# usb_isolated_uart_x2.net
KiCad netlist of a schematic drawn in Altium Designer
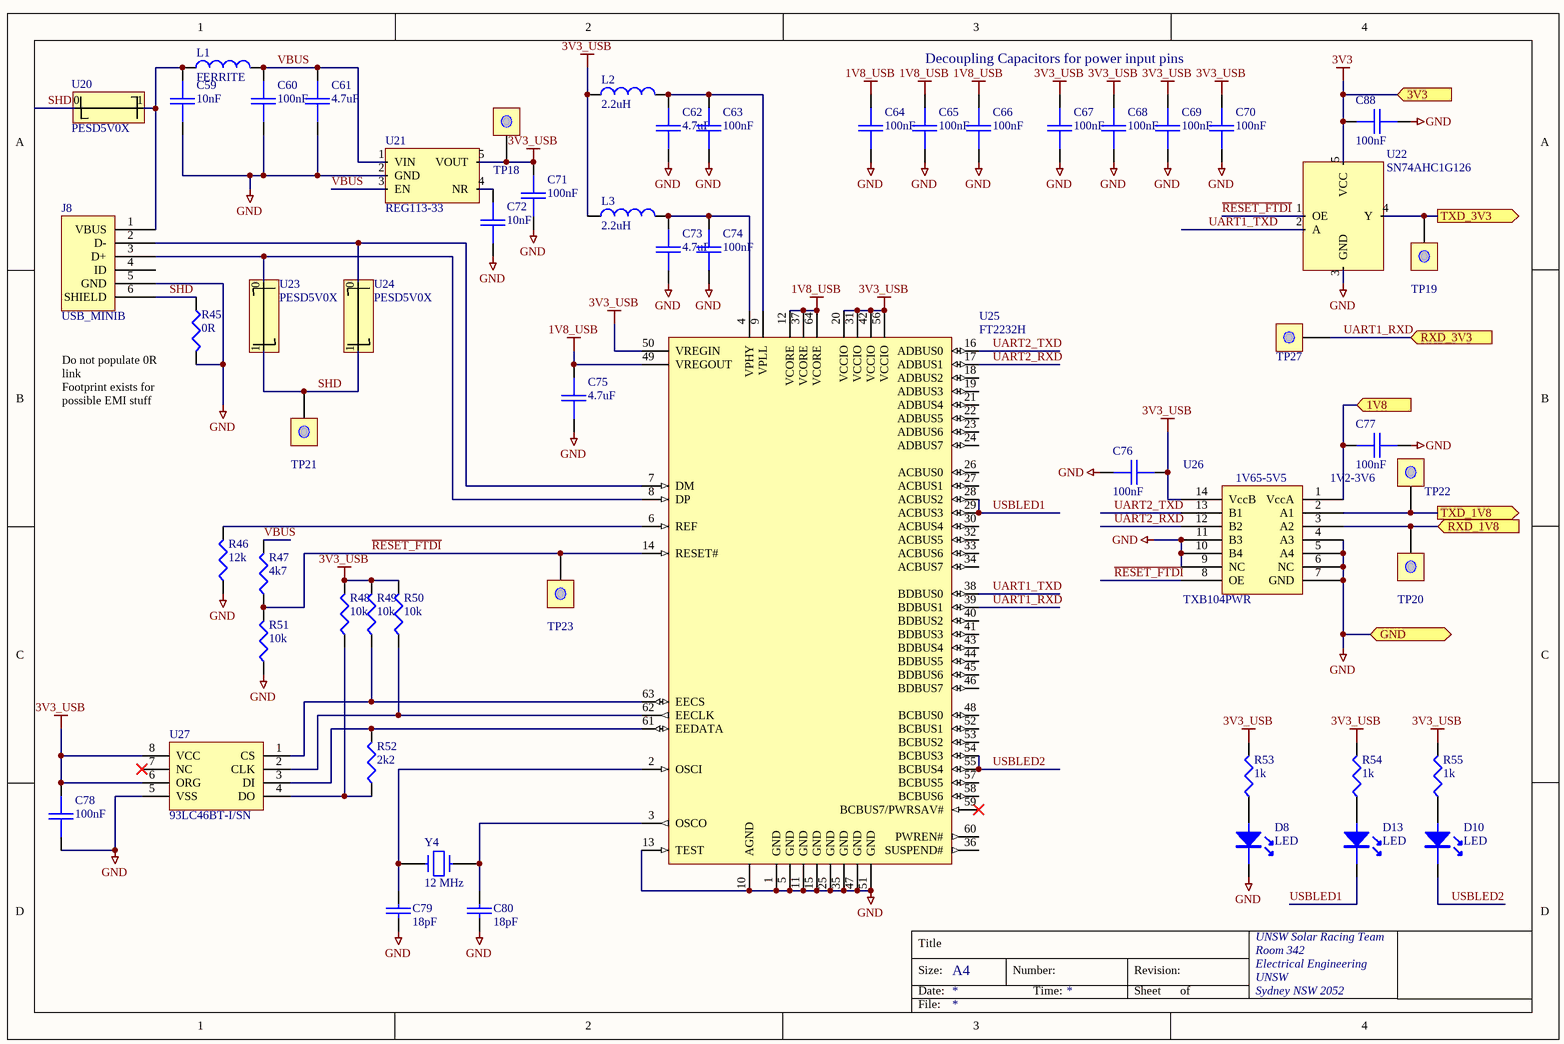
[diagram p0: usb_isolated_uart_x2.SchDoc]

(export (version "E")
  (design (tool "Eeschema 10.0.6"))
  (components
    (comp (ref "C59")
      (value "10nF")
      (footprint "0603")
      (description "Capacitor")
      (libsource (lib "RCLDQ") (part "CAP"))
    )
    (comp (ref "C60")
      (value "100nF")
      (footprint "0603")
      (description "Capacitor")
      (libsource (lib "RCLDQ") (part "CAP"))
    )
    (comp (ref "C61")
      (value "4.7uF")
      (footprint "0603")
      (description "Capacitor")
      (libsource (lib "RCLDQ") (part "CAP"))
    )
    (comp (ref "C62")
      (value "4.7uF")
      (footprint "0603")
      (description "Capacitor")
      (libsource (lib "RCLDQ") (part "CAP"))
    )
    (comp (ref "C63")
      (value "100nF")
      (footprint "0603")
      (description "Capacitor")
      (libsource (lib "RCLDQ") (part "CAP"))
    )
    (comp (ref "C64")
      (value "100nF")
      (footprint "0603")
      (description "Capacitor")
      (libsource (lib "RCLDQ") (part "CAP"))
    )
    (comp (ref "C65")
      (value "100nF")
      (footprint "0603")
      (description "Capacitor")
      (libsource (lib "RCLDQ") (part "CAP"))
    )
    (comp (ref "C66")
      (value "100nF")
      (footprint "0603")
      (description "Capacitor")
      (libsource (lib "RCLDQ") (part "CAP"))
    )
    (comp (ref "C67")
      (value "100nF")
      (footprint "0603")
      (description "Capacitor")
      (libsource (lib "RCLDQ") (part "CAP"))
    )
    (comp (ref "C68")
      (value "100nF")
      (footprint "0603")
      (description "Capacitor")
      (libsource (lib "RCLDQ") (part "CAP"))
    )
    (comp (ref "C69")
      (value "100nF")
      (footprint "0603")
      (description "Capacitor")
      (libsource (lib "RCLDQ") (part "CAP"))
    )
    (comp (ref "C70")
      (value "100nF")
      (footprint "0603")
      (description "Capacitor")
      (libsource (lib "RCLDQ") (part "CAP"))
    )
    (comp (ref "C71")
      (value "100nF")
      (footprint "0603")
      (description "Capacitor")
      (libsource (lib "RCLDQ") (part "CAP"))
    )
    (comp (ref "C72")
      (value "10nF")
      (footprint "0603")
      (description "Capacitor")
      (libsource (lib "RCLDQ") (part "CAP"))
    )
    (comp (ref "C73")
      (value "4.7uF")
      (footprint "0603")
      (description "Capacitor")
      (libsource (lib "RCLDQ") (part "CAP"))
    )
    (comp (ref "C74")
      (value "100nF")
      (footprint "0603")
      (description "Capacitor")
      (libsource (lib "RCLDQ") (part "CAP"))
    )
    (comp (ref "C75")
      (value "4.7uF")
      (footprint "0603")
      (description "Capacitor")
      (libsource (lib "RCLDQ") (part "CAP"))
    )
    (comp (ref "C76")
      (value "100nF")
      (footprint "0603")
      (description "Capacitor")
      (libsource (lib "RCLDQ") (part "CAP"))
    )
    (comp (ref "C77")
      (value "100nF")
      (footprint "0603")
      (description "Capacitor")
      (libsource (lib "RCLDQ") (part "CAP"))
    )
    (comp (ref "C78")
      (value "100nF")
      (footprint "0603")
      (description "Capacitor")
      (libsource (lib "RCLDQ") (part "CAP"))
    )
    (comp (ref "C79")
      (value "18pF")
      (footprint "0603")
      (description "Capacitor")
      (libsource (lib "*") (part "CAP"))
    )
    (comp (ref "C80")
      (value "18pF")
      (footprint "0603")
      (description "Capacitor")
      (libsource (lib "*") (part "CAP"))
    )
    (comp (ref "C88")
      (value "100nF")
      (footprint "0603")
      (description "Capacitor")
      (libsource (lib "RCLDQ") (part "CAP"))
    )
    (comp (ref "D8") (value "LED") (footprint "0805LED") (libsource (lib "RCLDQ") (part "LED")))
    (comp (ref "D10") (value "LED") (footprint "0805LED") (libsource (lib "RCLDQ") (part "LED")))
    (comp (ref "D13") (value "LED") (footprint "0805LED") (libsource (lib "RCLDQ") (part "LED")))
    (comp (ref "J8")
      (value "USB_MINIB")
      (footprint "USB_MINIB")
      (description "USB Mini B Connector")
      (libsource (lib "sion") (part "USB_miniB_SMT"))
    )
    (comp (ref "L1")
      (value "FERRITE")
      (footprint "0603")
      (description "Inductor")
      (libsource (lib "RCLDQ") (part "INDUCTOR"))
    )
    (comp (ref "L2")
      (value "2.2uH")
      (footprint "1210")
      (description "Inductor")
      (libsource (lib "RCLDQ") (part "INDUCTOR"))
    )
    (comp (ref "L3")
      (value "2.2uH")
      (footprint "1210")
      (description "Inductor")
      (libsource (lib "RCLDQ") (part "INDUCTOR"))
    )
    (comp (ref "R45")
      (value "0R")
      (footprint "1206")
      (description "Resistor")
      (libsource (lib "RCLDQ") (part "RES1"))
    )
    (comp (ref "R46")
      (value "12k")
      (footprint "0603")
      (description "Resistor")
      (libsource (lib "RCLDQ") (part "RES1"))
    )
    (comp (ref "R47")
      (value "4k7")
      (footprint "0603")
      (description "Resistor")
      (libsource (lib "RCLDQ") (part "RES1"))
    )
    (comp (ref "R48")
      (value "10k")
      (footprint "0603")
      (description "Resistor")
      (libsource (lib "RCLDQ") (part "RES1"))
    )
    (comp (ref "R49")
      (value "10k")
      (footprint "0603")
      (description "Resistor")
      (libsource (lib "RCLDQ") (part "RES1"))
    )
    (comp (ref "R50")
      (value "10k")
      (footprint "0603")
      (description "Resistor")
      (libsource (lib "RCLDQ") (part "RES1"))
    )
    (comp (ref "R51")
      (value "10k")
      (footprint "0603")
      (description "Resistor")
      (libsource (lib "RCLDQ") (part "RES1"))
    )
    (comp (ref "R52")
      (value "2k2")
      (footprint "0603")
      (description "Resistor")
      (libsource (lib "RCLDQ") (part "RES1"))
    )
    (comp (ref "R53")
      (value "1k")
      (footprint "0603")
      (description "Resistor")
      (libsource (lib "RCLDQ") (part "RES1"))
    )
    (comp (ref "R54")
      (value "1k")
      (footprint "0603")
      (description "Resistor")
      (libsource (lib "RCLDQ") (part "RES1"))
    )
    (comp (ref "R55")
      (value "1k")
      (footprint "0603")
      (description "Resistor")
      (libsource (lib "RCLDQ") (part "RES1"))
    )
    (comp (ref "TP18")
      (value "3V3USB")
      (footprint "TESTPOINT")
      (description "TEST POINT")
      (libsource (lib "Miscellaneous") (part "TEST"))
    )
    (comp (ref "TP19")
      (value "TXD3V3")
      (footprint "TESTPOINT")
      (description "TEST POINT")
      (libsource (lib "") (part "TEST_1"))
    )
    (comp (ref "TP20")
      (value "RXD1V8")
      (footprint "TESTPOINT")
      (description "TEST POINT")
      (libsource (lib "") (part "TEST_1"))
    )
    (comp (ref "TP21")
      (value "SHD")
      (footprint "TESTPOINT")
      (description "TEST POINT")
      (libsource (lib "") (part "TEST_1"))
    )
    (comp (ref "TP22")
      (value "TXD1V8")
      (footprint "TESTPOINT")
      (description "TEST POINT")
      (libsource (lib "Miscellaneous") (part "TEST"))
    )
    (comp (ref "TP23")
      (value "FTDI_RST")
      (footprint "TESTPOINT")
      (description "TEST POINT")
      (libsource (lib "") (part "TEST_1"))
    )
    (comp (ref "TP27")
      (value "RXD3V3")
      (footprint "TESTPOINT")
      (description "TEST POINT")
      (libsource (lib "") (part "TEST_2"))
    )
    (comp (ref "U20")
      (value "PESD5V0X")
      (footprint "SOD323")
      (description "Ultra low capacitance bidirectional ESD protection diodes")
      (libsource (lib "gumstix") (part "PESD5V0X"))
    )
    (comp (ref "U21")
      (value "REG113-33")
      (footprint "SOT23-5")
      (description "400mA Low-Dropout Regulator")
      (libsource (lib "gumstix") (part "REG113-33"))
    )
    (comp (ref "U22")
      (value "SN74AHC1G126")
      (footprint "SOT23-5")
      (description "Single Bus Buffer Gate with 3 State Output")
      (libsource (lib "gumstix") (part "SN74AHC1G126"))
    )
    (comp (ref "U23")
      (value "PESD5V0X")
      (footprint "SOD323")
      (description "Ultra low capacitance bidirectional ESD protection diodes")
      (libsource (lib "") (part "PESD5V0X_1"))
    )
    (comp (ref "U24")
      (value "PESD5V0X")
      (footprint "SOD323")
      (description "Ultra low capacitance bidirectional ESD protection diodes")
      (libsource (lib "") (part "PESD5V0X_1"))
    )
    (comp (ref "U25")
      (value "FT2232H")
      (footprint "QFP64")
      (description "Dual USB to UART/FIFO")
      (libsource (lib "sion") (part "FT2232H"))
    )
    (comp (ref "U26")
      (value "TXB104PWR")
      (footprint "TSSOP14-L")
      (description "4 bit bidirectional auto direction sense level translator")
      (libsource (lib "sion") (part "TXB0104PWR"))
    )
    (comp (ref "U27")
      (value "93LC46BT-I/SN")
      (footprint "SO8")
      (description "Serial EEPROM")
      (libsource (lib "sion") (part "93LC46BT-I/SN"))
    )
    (comp (ref "Y4")
      (value "12 MHz")
      (footprint "HC49/4H")
      (description "Crystal")
      (libsource (lib "*") (part "CRYSTAL"))
    )
  )
  (nets
    (net (code "1") (name "/1V8") (class "Default")
      (node (ref "C77") (pin "1") (pinfunction "1_1") (pintype "passive"))
      (node (ref "U26") (pin "1") (pinfunction "VccA_1") (pintype "power_in"))
    )
    (net (code "2") (name "/RESET_FTDI") (class "Default")
      (node (ref "R47") (pin "1") (pinfunction "1_1") (pintype "passive"))
      (node (ref "R51") (pin "2") (pinfunction "2_2") (pintype "passive"))
      (node (ref "TP23") (pin "0") (pinfunction "TP_0") (pintype "passive"))
      (node (ref "U22") (pin "1") (pinfunction "OE_1") (pintype "passive"))
      (node (ref "U25") (pin "14") (pinfunction "RESET#_14") (pintype "input"))
      (node (ref "U26") (pin "8") (pinfunction "OE_8") (pintype "passive"))
    )
    (net (code "3") (name "/RXD_1V8") (class "Default")
      (node (ref "TP20") (pin "0") (pinfunction "TP_0") (pintype "passive"))
      (node (ref "U26") (pin "3") (pinfunction "A2_3") (pintype "passive"))
    )
    (net (code "4") (name "/SHD") (class "Default")
      (node (ref "J8") (pin "6") (pinfunction "SHIELD_6") (pintype "passive"))
      (node (ref "R45") (pin "1") (pinfunction "1_1") (pintype "passive"))
      (node (ref "TP21") (pin "0") (pinfunction "TP_0") (pintype "passive"))
      (node (ref "U20") (pin "0") (pintype "passive"))
      (node (ref "U23") (pin "1") (pintype "passive"))
      (node (ref "U24") (pin "1") (pintype "passive"))
    )
    (net (code "5") (name "/TXD_1V8") (class "Default")
      (node (ref "TP22") (pin "0") (pinfunction "TP_0") (pintype "passive"))
      (node (ref "U26") (pin "2") (pinfunction "A1_2") (pintype "passive"))
    )
    (net (code "6") (name "/TXD_3V3") (class "Default")
      (node (ref "TP19") (pin "0") (pinfunction "TP_0") (pintype "passive"))
      (node (ref "U22") (pin "4") (pinfunction "Y_4") (pintype "passive"))
    )
    (net (code "7") (name "/UART1_RXD") (class "Default")
      (node (ref "TP27") (pin "0") (pinfunction "TP_0") (pintype "passive"))
      (node (ref "U25") (pin "39") (pinfunction "BDBUS1_39") (pintype "bidirectional"))
    )
    (net (code "8") (name "/UART1_TXD") (class "Default")
      (node (ref "U22") (pin "2") (pinfunction "A_2") (pintype "passive"))
      (node (ref "U25") (pin "38") (pinfunction "BDBUS0_38") (pintype "bidirectional"))
    )
    (net (code "9") (name "/UART2_RXD") (class "Default")
      (node (ref "U25") (pin "17") (pinfunction "ADBUS1_17") (pintype "bidirectional"))
      (node (ref "U26") (pin "12") (pinfunction "B2_12") (pintype "passive"))
    )
    (net (code "10") (name "/UART2_TXD") (class "Default")
      (node (ref "U25") (pin "16") (pinfunction "ADBUS0_16") (pintype "bidirectional"))
      (node (ref "U26") (pin "13") (pinfunction "B1_13") (pintype "passive"))
    )
    (net (code "11") (name "/USBLED1") (class "Default")
      (node (ref "D13") (pin "K") (pinfunction "K_K") (pintype "passive"))
      (node (ref "U25") (pin "28") (pinfunction "ACBUS2_28") (pintype "bidirectional"))
      (node (ref "U25") (pin "29") (pinfunction "ACBUS3_29") (pintype "bidirectional"))
    )
    (net (code "12") (name "/USBLED2") (class "Default")
      (node (ref "D10") (pin "K") (pinfunction "K_K") (pintype "passive"))
      (node (ref "U25") (pin "54") (pinfunction "BCBUS3_54") (pintype "bidirectional"))
      (node (ref "U25") (pin "55") (pinfunction "BCBUS4_55") (pintype "bidirectional"))
    )
    (net (code "13") (name "/VBUS") (class "Default")
      (node (ref "C60") (pin "1") (pinfunction "1_1") (pintype "passive"))
      (node (ref "C61") (pin "1") (pinfunction "1_1") (pintype "passive"))
      (node (ref "L1") (pin "2") (pinfunction "2_2") (pintype "passive"))
      (node (ref "R47") (pin "2") (pinfunction "2_2") (pintype "passive"))
      (node (ref "U21") (pin "1") (pinfunction "VIN_1") (pintype "passive"))
      (node (ref "U21") (pin "3") (pinfunction "EN_3") (pintype "passive"))
    )
    (net (code "14") (name "1V8_USB") (class "Default")
      (node (ref "C64") (pin "1") (pinfunction "1_1") (pintype "passive"))
      (node (ref "C65") (pin "1") (pinfunction "1_1") (pintype "passive"))
      (node (ref "C66") (pin "1") (pinfunction "1_1") (pintype "passive"))
      (node (ref "C75") (pin "1") (pinfunction "1_1") (pintype "passive"))
      (node (ref "U25") (pin "12") (pinfunction "VCORE_12") (pintype "power_in"))
      (node (ref "U25") (pin "37") (pinfunction "VCORE_37") (pintype "power_in"))
      (node (ref "U25") (pin "49") (pinfunction "VREGOUT_49") (pintype "power_in"))
      (node (ref "U25") (pin "64") (pinfunction "VCORE_64") (pintype "power_in"))
    )
    (net (code "15") (name "3V3") (class "Default")
      (node (ref "C88") (pin "2") (pinfunction "2_2") (pintype "passive"))
      (node (ref "U22") (pin "5") (pinfunction "VCC_5") (pintype "passive"))
    )
    (net (code "16") (name "3V3_USB") (class "Default")
      (node (ref "C67") (pin "1") (pinfunction "1_1") (pintype "passive"))
      (node (ref "C68") (pin "1") (pinfunction "1_1") (pintype "passive"))
      (node (ref "C69") (pin "1") (pinfunction "1_1") (pintype "passive"))
      (node (ref "C70") (pin "1") (pinfunction "1_1") (pintype "passive"))
      (node (ref "C71") (pin "1") (pinfunction "1_1") (pintype "passive"))
      (node (ref "C76") (pin "2") (pinfunction "2_2") (pintype "passive"))
      (node (ref "C78") (pin "1") (pinfunction "1_1") (pintype "passive"))
      (node (ref "L2") (pin "1") (pinfunction "1_1") (pintype "passive"))
      (node (ref "L3") (pin "1") (pinfunction "1_1") (pintype "passive"))
      (node (ref "R48") (pin "2") (pinfunction "2_2") (pintype "passive"))
      (node (ref "R49") (pin "2") (pinfunction "2_2") (pintype "passive"))
      (node (ref "R50") (pin "2") (pinfunction "2_2") (pintype "passive"))
      (node (ref "R53") (pin "2") (pinfunction "2_2") (pintype "passive"))
      (node (ref "R54") (pin "2") (pinfunction "2_2") (pintype "passive"))
      (node (ref "R55") (pin "2") (pinfunction "2_2") (pintype "passive"))
      (node (ref "TP18") (pin "0") (pinfunction "TP_0") (pintype "passive"))
      (node (ref "U21") (pin "5") (pinfunction "VOUT_5") (pintype "passive"))
      (node (ref "U25") (pin "20") (pinfunction "VCCIO_20") (pintype "power_in"))
      (node (ref "U25") (pin "31") (pinfunction "VCCIO_31") (pintype "power_in"))
      (node (ref "U25") (pin "42") (pinfunction "VCCIO_42") (pintype "power_in"))
      (node (ref "U25") (pin "50") (pinfunction "VREGIN_50") (pintype "power_in"))
      (node (ref "U25") (pin "56") (pinfunction "VCCIO_56") (pintype "power_in"))
      (node (ref "U26") (pin "14") (pinfunction "VccB_14") (pintype "power_in"))
      (node (ref "U27") (pin "6") (pinfunction "ORG_6") (pintype "passive"))
      (node (ref "U27") (pin "8") (pinfunction "VCC_8") (pintype "passive"))
    )
    (net (code "17") (name "GND") (class "Default")
      (node (ref "C59") (pin "1") (pinfunction "1_1") (pintype "passive"))
      (node (ref "C60") (pin "2") (pinfunction "2_2") (pintype "passive"))
      (node (ref "C61") (pin "2") (pinfunction "2_2") (pintype "passive"))
      (node (ref "C62") (pin "2") (pinfunction "2_2") (pintype "passive"))
      (node (ref "C63") (pin "2") (pinfunction "2_2") (pintype "passive"))
      (node (ref "C64") (pin "2") (pinfunction "2_2") (pintype "passive"))
      (node (ref "C65") (pin "2") (pinfunction "2_2") (pintype "passive"))
      (node (ref "C66") (pin "2") (pinfunction "2_2") (pintype "passive"))
      (node (ref "C67") (pin "2") (pinfunction "2_2") (pintype "passive"))
      (node (ref "C68") (pin "2") (pinfunction "2_2") (pintype "passive"))
      (node (ref "C69") (pin "2") (pinfunction "2_2") (pintype "passive"))
      (node (ref "C70") (pin "2") (pinfunction "2_2") (pintype "passive"))
      (node (ref "C71") (pin "2") (pinfunction "2_2") (pintype "passive"))
      (node (ref "C72") (pin "2") (pinfunction "2_2") (pintype "passive"))
      (node (ref "C73") (pin "2") (pinfunction "2_2") (pintype "passive"))
      (node (ref "C74") (pin "2") (pinfunction "2_2") (pintype "passive"))
      (node (ref "C75") (pin "2") (pinfunction "2_2") (pintype "passive"))
      (node (ref "C76") (pin "1") (pinfunction "1_1") (pintype "passive"))
      (node (ref "C77") (pin "2") (pinfunction "2_2") (pintype "passive"))
      (node (ref "C78") (pin "2") (pinfunction "2_2") (pintype "passive"))
      (node (ref "C79") (pin "2") (pinfunction "2_2") (pintype "passive"))
      (node (ref "C80") (pin "2") (pinfunction "2_2") (pintype "passive"))
      (node (ref "C88") (pin "1") (pinfunction "1_1") (pintype "passive"))
      (node (ref "D8") (pin "K") (pinfunction "K_K") (pintype "passive"))
      (node (ref "J8") (pin "5") (pinfunction "GND_5") (pintype "passive"))
      (node (ref "R45") (pin "2") (pinfunction "2_2") (pintype "passive"))
      (node (ref "R46") (pin "1") (pinfunction "1_1") (pintype "passive"))
      (node (ref "R51") (pin "1") (pinfunction "1_1") (pintype "passive"))
      (node (ref "U21") (pin "2") (pinfunction "GND_2") (pintype "passive"))
      (node (ref "U22") (pin "3") (pinfunction "GND_3") (pintype "passive"))
      (node (ref "U25") (pin "1") (pinfunction "GND_1") (pintype "power_in"))
      (node (ref "U25") (pin "10") (pinfunction "AGND_10") (pintype "power_in"))
      (node (ref "U25") (pin "11") (pinfunction "GND_11") (pintype "power_in"))
      (node (ref "U25") (pin "13") (pinfunction "TEST_13") (pintype "input"))
      (node (ref "U25") (pin "15") (pinfunction "GND_15") (pintype "power_in"))
      (node (ref "U25") (pin "25") (pinfunction "GND_25") (pintype "power_in"))
      (node (ref "U25") (pin "35") (pinfunction "GND_35") (pintype "power_in"))
      (node (ref "U25") (pin "47") (pinfunction "GND_47") (pintype "power_in"))
      (node (ref "U25") (pin "5") (pinfunction "GND_5") (pintype "power_in"))
      (node (ref "U25") (pin "51") (pinfunction "GND_51") (pintype "power_in"))
      (node (ref "U26") (pin "10") (pinfunction "B4_10") (pintype "passive"))
      (node (ref "U26") (pin "11") (pinfunction "B3_11") (pintype "passive"))
      (node (ref "U26") (pin "4") (pinfunction "A3_4") (pintype "passive"))
      (node (ref "U26") (pin "5") (pinfunction "A4_5") (pintype "passive"))
      (node (ref "U26") (pin "6") (pinfunction "NC_6") (pintype "passive"))
      (node (ref "U26") (pin "7") (pinfunction "GND_7") (pintype "power_in"))
      (node (ref "U26") (pin "9") (pinfunction "NC_9") (pintype "passive"))
      (node (ref "U27") (pin "5") (pinfunction "VSS_5") (pintype "passive"))
    )
    (net (code "18") (name "Net-(D8-PadA)") (class "Default")
      (node (ref "D8") (pin "A") (pinfunction "A_A") (pintype "passive"))
      (node (ref "R53") (pin "1") (pinfunction "1_1") (pintype "passive"))
    )
    (net (code "19") (name "Net-(D10-PadA)") (class "Default")
      (node (ref "D10") (pin "A") (pinfunction "A_A") (pintype "passive"))
      (node (ref "R55") (pin "1") (pinfunction "1_1") (pintype "passive"))
    )
    (net (code "20") (name "Net-(D13-PadA)") (class "Default")
      (node (ref "D13") (pin "A") (pinfunction "A_A") (pintype "passive"))
      (node (ref "R54") (pin "1") (pinfunction "1_1") (pintype "passive"))
    )
    (net (code "21") (name "Net-(J8-D+)") (class "Default")
      (node (ref "J8") (pin "3") (pinfunction "D+_3") (pintype "passive"))
      (node (ref "U23") (pin "0") (pintype "passive"))
      (node (ref "U25") (pin "8") (pinfunction "DP_8") (pintype "input"))
    )
    (net (code "22") (name "Net-(J8-D-)") (class "Default")
      (node (ref "J8") (pin "2") (pinfunction "D-_2") (pintype "passive"))
      (node (ref "U24") (pin "0") (pintype "passive"))
      (node (ref "U25") (pin "7") (pinfunction "DM_7") (pintype "input"))
    )
    (net (code "23") (name "Net-(J8-VBUS)") (class "Default")
      (node (ref "C59") (pin "2") (pinfunction "2_2") (pintype "passive"))
      (node (ref "J8") (pin "1") (pinfunction "VBUS_1") (pintype "passive"))
      (node (ref "L1") (pin "1") (pinfunction "1_1") (pintype "passive"))
      (node (ref "U20") (pin "1") (pintype "passive"))
    )
    (net (code "24") (name "Net-(U21-NR)") (class "Default")
      (node (ref "C72") (pin "1") (pinfunction "1_1") (pintype "passive"))
      (node (ref "U21") (pin "4") (pinfunction "NR_4") (pintype "passive"))
    )
    (net (code "25") (name "Net-(U25-EECLK)") (class "Default")
      (node (ref "R50") (pin "1") (pinfunction "1_1") (pintype "passive"))
      (node (ref "U25") (pin "62") (pinfunction "EECLK_62") (pintype "output"))
      (node (ref "U27") (pin "2") (pinfunction "CLK_2") (pintype "passive"))
    )
    (net (code "26") (name "Net-(U25-EECS)") (class "Default")
      (node (ref "R49") (pin "1") (pinfunction "1_1") (pintype "passive"))
      (node (ref "U25") (pin "63") (pinfunction "EECS_63") (pintype "bidirectional"))
      (node (ref "U27") (pin "1") (pinfunction "CS_1") (pintype "passive"))
    )
    (net (code "27") (name "Net-(U25-EEDATA)") (class "Default")
      (node (ref "R52") (pin "2") (pinfunction "2_2") (pintype "passive"))
      (node (ref "U25") (pin "61") (pinfunction "EEDATA_61") (pintype "bidirectional"))
      (node (ref "U27") (pin "3") (pinfunction "DI_3") (pintype "passive"))
    )
    (net (code "28") (name "Net-(U25-OSCI)") (class "Default")
      (node (ref "C79") (pin "1") (pinfunction "1_1") (pintype "passive"))
      (node (ref "U25") (pin "2") (pinfunction "OSCI_2") (pintype "input"))
      (node (ref "Y4") (pin "2") (pinfunction "2_2") (pintype "passive"))
    )
    (net (code "29") (name "Net-(U25-OSCO)") (class "Default")
      (node (ref "C80") (pin "1") (pinfunction "1_1") (pintype "passive"))
      (node (ref "U25") (pin "3") (pinfunction "OSCO_3") (pintype "output"))
      (node (ref "Y4") (pin "1") (pinfunction "1_1") (pintype "passive"))
    )
    (net (code "30") (name "Net-(U25-REF)") (class "Default")
      (node (ref "R46") (pin "2") (pinfunction "2_2") (pintype "passive"))
      (node (ref "U25") (pin "6") (pinfunction "REF_6") (pintype "input"))
    )
    (net (code "31") (name "Net-(U25-VPHY)") (class "Default")
      (node (ref "C73") (pin "1") (pinfunction "1_1") (pintype "passive"))
      (node (ref "C74") (pin "1") (pinfunction "1_1") (pintype "passive"))
      (node (ref "L3") (pin "2") (pinfunction "2_2") (pintype "passive"))
      (node (ref "U25") (pin "4") (pinfunction "VPHY_4") (pintype "power_in"))
    )
    (net (code "32") (name "Net-(U25-VPLL)") (class "Default")
      (node (ref "C62") (pin "1") (pinfunction "1_1") (pintype "passive"))
      (node (ref "C63") (pin "1") (pinfunction "1_1") (pintype "passive"))
      (node (ref "L2") (pin "2") (pinfunction "2_2") (pintype "passive"))
      (node (ref "U25") (pin "9") (pinfunction "VPLL_9") (pintype "power_in"))
    )
    (net (code "33") (name "Net-(U27-DO)") (class "Default")
      (node (ref "R48") (pin "1") (pinfunction "1_1") (pintype "passive"))
      (node (ref "R52") (pin "1") (pinfunction "1_1") (pintype "passive"))
      (node (ref "U27") (pin "4") (pinfunction "DO_4") (pintype "passive"))
    )
    (net (code "34") (name "unconnected-(J8-ID-Pad4)") (class "Default")
      (node (ref "J8") (pin "4") (pinfunction "ID_4") (pintype "passive"))
    )
    (net (code "35") (name "unconnected-(U25-ACBUS0-Pad26)") (class "Default")
      (node (ref "U25") (pin "26") (pinfunction "ACBUS0_26") (pintype "bidirectional"))
    )
    (net (code "36") (name "unconnected-(U25-ACBUS1-Pad27)") (class "Default")
      (node (ref "U25") (pin "27") (pinfunction "ACBUS1_27") (pintype "bidirectional"))
    )
    (net (code "37") (name "unconnected-(U25-ACBUS4-Pad30)") (class "Default")
      (node (ref "U25") (pin "30") (pinfunction "ACBUS4_30") (pintype "bidirectional"))
    )
    (net (code "38") (name "unconnected-(U25-ACBUS5-Pad32)") (class "Default")
      (node (ref "U25") (pin "32") (pinfunction "ACBUS5_32") (pintype "bidirectional"))
    )
    (net (code "39") (name "unconnected-(U25-ACBUS6-Pad33)") (class "Default")
      (node (ref "U25") (pin "33") (pinfunction "ACBUS6_33") (pintype "bidirectional"))
    )
    (net (code "40") (name "unconnected-(U25-ACBUS7-Pad34)") (class "Default")
      (node (ref "U25") (pin "34") (pinfunction "ACBUS7_34") (pintype "bidirectional"))
    )
    (net (code "41") (name "unconnected-(U25-ADBUS2-Pad18)") (class "Default")
      (node (ref "U25") (pin "18") (pinfunction "ADBUS2_18") (pintype "bidirectional"))
    )
    (net (code "42") (name "unconnected-(U25-ADBUS3-Pad19)") (class "Default")
      (node (ref "U25") (pin "19") (pinfunction "ADBUS3_19") (pintype "bidirectional"))
    )
    (net (code "43") (name "unconnected-(U25-ADBUS4-Pad21)") (class "Default")
      (node (ref "U25") (pin "21") (pinfunction "ADBUS4_21") (pintype "bidirectional"))
    )
    (net (code "44") (name "unconnected-(U25-ADBUS5-Pad22)") (class "Default")
      (node (ref "U25") (pin "22") (pinfunction "ADBUS5_22") (pintype "bidirectional"))
    )
    (net (code "45") (name "unconnected-(U25-ADBUS6-Pad23)") (class "Default")
      (node (ref "U25") (pin "23") (pinfunction "ADBUS6_23") (pintype "bidirectional"))
    )
    (net (code "46") (name "unconnected-(U25-ADBUS7-Pad24)") (class "Default")
      (node (ref "U25") (pin "24") (pinfunction "ADBUS7_24") (pintype "bidirectional"))
    )
    (net (code "47") (name "unconnected-(U25-BCBUS0-Pad48)") (class "Default")
      (node (ref "U25") (pin "48") (pinfunction "BCBUS0_48") (pintype "bidirectional"))
    )
    (net (code "48") (name "unconnected-(U25-BCBUS1-Pad52)") (class "Default")
      (node (ref "U25") (pin "52") (pinfunction "BCBUS1_52") (pintype "bidirectional"))
    )
    (net (code "49") (name "unconnected-(U25-BCBUS2-Pad53)") (class "Default")
      (node (ref "U25") (pin "53") (pinfunction "BCBUS2_53") (pintype "bidirectional"))
    )
    (net (code "50") (name "unconnected-(U25-BCBUS5-Pad57)") (class "Default")
      (node (ref "U25") (pin "57") (pinfunction "BCBUS5_57") (pintype "bidirectional"))
    )
    (net (code "51") (name "unconnected-(U25-BCBUS6-Pad58)") (class "Default")
      (node (ref "U25") (pin "58") (pinfunction "BCBUS6_58") (pintype "bidirectional"))
    )
    (net (code "52") (name "unconnected-(U25-BCBUS7{slash}PWRSAV#-Pad59)") (class "Default")
      (node (ref "U25") (pin "59") (pinfunction "BCBUS7/PWRSAV#_59") (pintype "input+no_connect"))
    )
    (net (code "53") (name "unconnected-(U25-BDBUS2-Pad40)") (class "Default")
      (node (ref "U25") (pin "40") (pinfunction "BDBUS2_40") (pintype "bidirectional"))
    )
    (net (code "54") (name "unconnected-(U25-BDBUS3-Pad41)") (class "Default")
      (node (ref "U25") (pin "41") (pinfunction "BDBUS3_41") (pintype "bidirectional"))
    )
    (net (code "55") (name "unconnected-(U25-BDBUS4-Pad43)") (class "Default")
      (node (ref "U25") (pin "43") (pinfunction "BDBUS4_43") (pintype "bidirectional"))
    )
    (net (code "56") (name "unconnected-(U25-BDBUS5-Pad44)") (class "Default")
      (node (ref "U25") (pin "44") (pinfunction "BDBUS5_44") (pintype "bidirectional"))
    )
    (net (code "57") (name "unconnected-(U25-BDBUS6-Pad45)") (class "Default")
      (node (ref "U25") (pin "45") (pinfunction "BDBUS6_45") (pintype "bidirectional"))
    )
    (net (code "58") (name "unconnected-(U25-BDBUS7-Pad46)") (class "Default")
      (node (ref "U25") (pin "46") (pinfunction "BDBUS7_46") (pintype "bidirectional"))
    )
    (net (code "59") (name "unconnected-(U25-PWREN#-Pad60)") (class "Default")
      (node (ref "U25") (pin "60") (pinfunction "PWREN#_60") (pintype "output"))
    )
    (net (code "60") (name "unconnected-(U25-SUSPEND#-Pad36)") (class "Default")
      (node (ref "U25") (pin "36") (pinfunction "SUSPEND#_36") (pintype "output"))
    )
    (net (code "61") (name "unconnected-(U27-NC-Pad7)") (class "Default")
      (node (ref "U27") (pin "7") (pinfunction "NC_7") (pintype "passive+no_connect"))
    )
  )
)
